# Board_Schamatic06.net
KiCad netlist of a schematic drawn in EAGLE
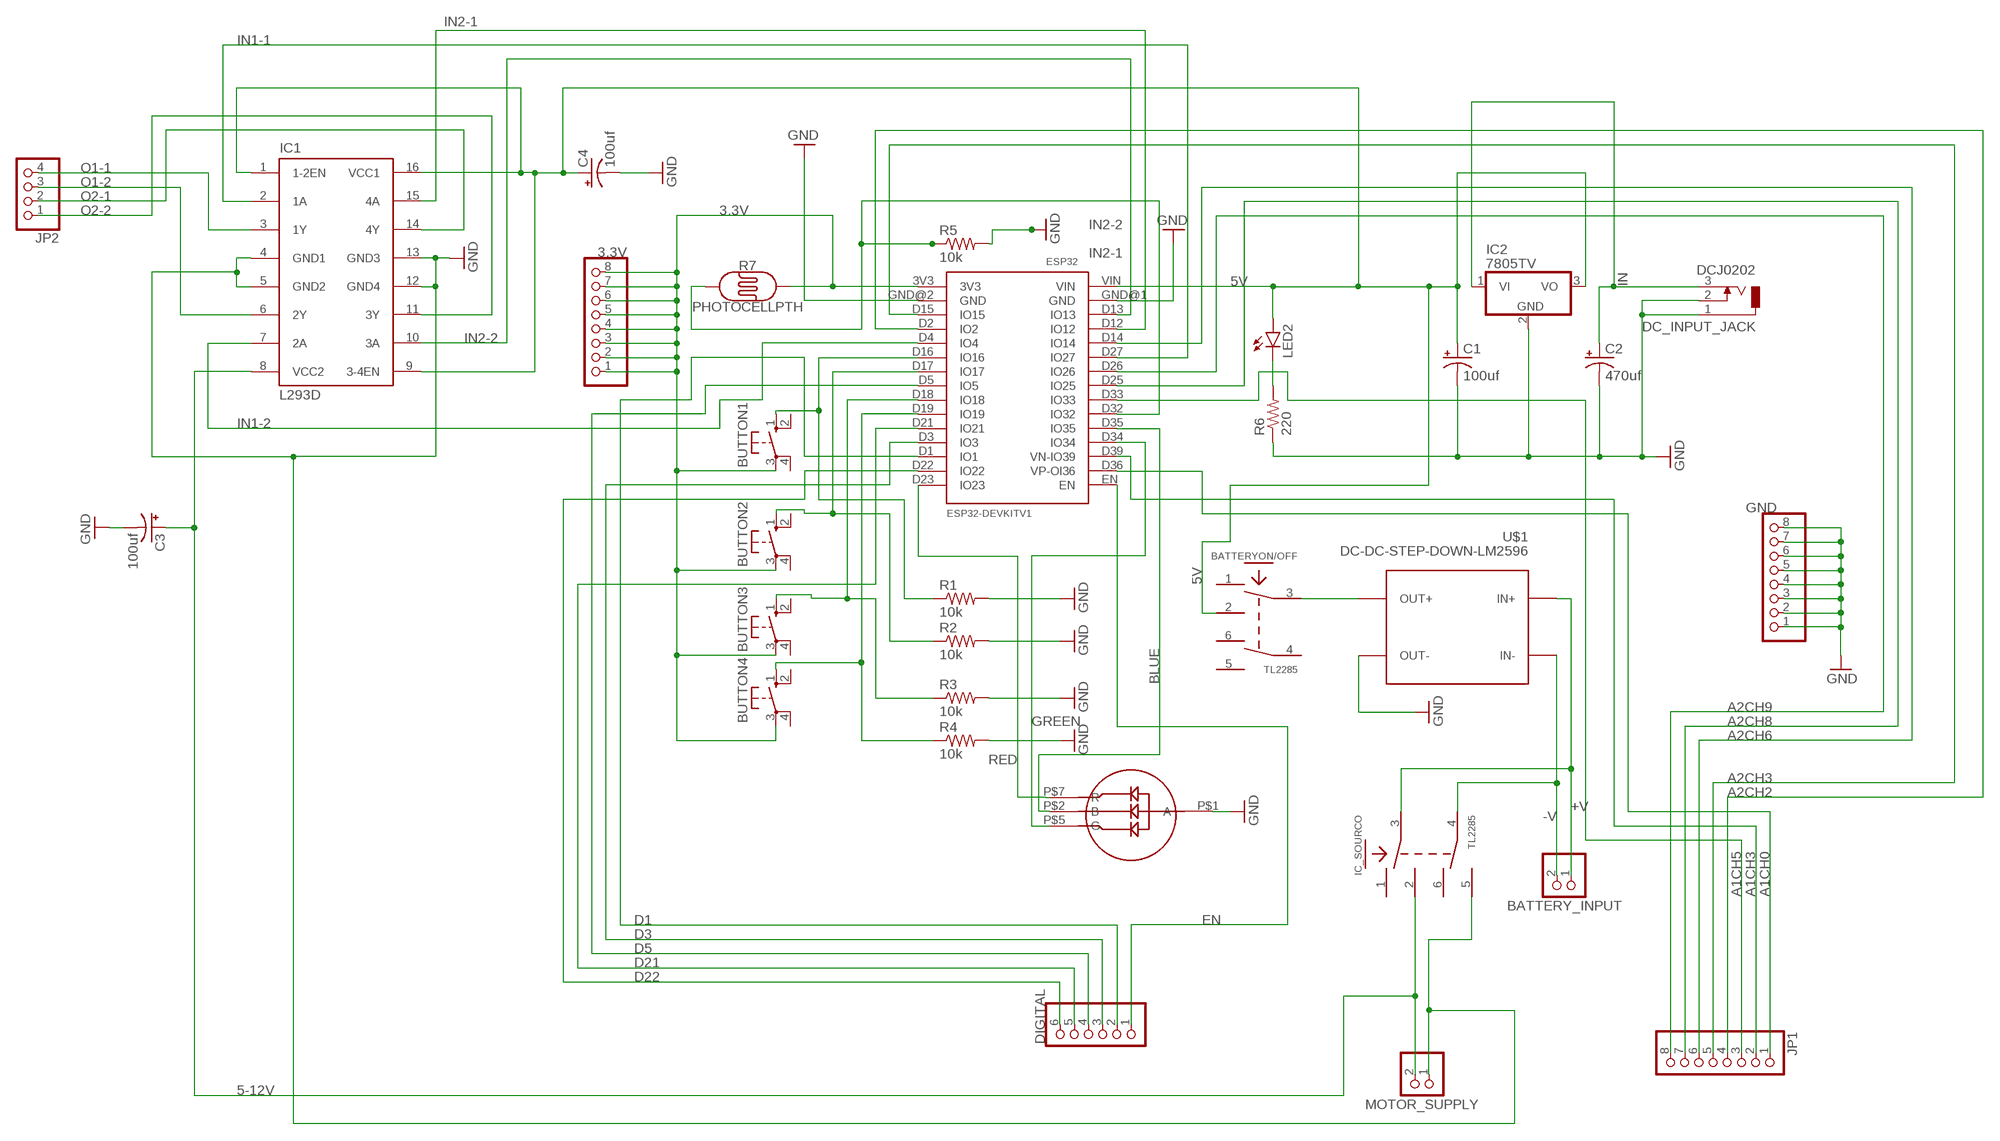
[diagram p0: schematic, sheet 1]

(export (version "E")
  (design (tool "Eeschema 10.0.6"))
  (components
    (comp (ref "3.3V")
      (value "PINHD-1X8")
      (footprint "eagle-import:1X08")
      (libsource (lib "eagle-import") (part "PINHD-1X8"))
    )
    (comp (ref "BATTERYON/OFF")
      (value "TL2285")
      (footprint "eagle-import:TL2285_PCB")
      (libsource (lib "eagle-import") (part "TL2285"))
    )
    (comp (ref "BATTERY_INPUT")
      (value "PINHD-1X2")
      (footprint "eagle-import:1X02")
      (libsource (lib "eagle-import") (part "PINHD-1X2"))
    )
    (comp (ref "BUTTON1")
      (value "10-XX")
      (footprint "eagle-import:B3F-10XX")
      (fields (field (name "MPN") "B3F-1000"))
      (libsource (lib "eagle-import") (part "10-XX"))
    )
    (comp (ref "BUTTON2")
      (value "10-XX")
      (footprint "eagle-import:B3F-10XX")
      (fields (field (name "MPN") "B3F-1000"))
      (libsource (lib "eagle-import") (part "10-XX"))
    )
    (comp (ref "BUTTON3")
      (value "10-XX")
      (footprint "eagle-import:B3F-10XX")
      (fields (field (name "MPN") "B3F-1000"))
      (libsource (lib "eagle-import") (part "10-XX"))
    )
    (comp (ref "BUTTON4")
      (value "10-XX")
      (footprint "eagle-import:B3F-10XX")
      (fields (field (name "MPN") "B3F-1000"))
      (libsource (lib "eagle-import") (part "10-XX"))
    )
    (comp (ref "C1")
      (value "100uf")
      (footprint "eagle-import:E2-5")
      (libsource (lib "eagle-import") (part "CPOL-USE2-5"))
    )
    (comp (ref "C2")
      (value "470uf")
      (footprint "eagle-import:E2-5")
      (libsource (lib "eagle-import") (part "CPOL-USE2-5"))
    )
    (comp (ref "C3")
      (value "100uf")
      (footprint "eagle-import:E2-5")
      (libsource (lib "eagle-import") (part "CPOL-USE2-5"))
    )
    (comp (ref "C4")
      (value "100uf")
      (footprint "eagle-import:E2-5")
      (libsource (lib "eagle-import") (part "CPOL-USE2-5"))
    )
    (comp (ref "DC_INPUT_JACK")
      (value "DCJ0202")
      (footprint "eagle-import:DCJ0202")
      (libsource (lib "eagle-import") (part "DCJ0202"))
    )
    (comp (ref "DIGITAL")
      (value "PINHD-1X6")
      (footprint "eagle-import:1X06")
      (libsource (lib "eagle-import") (part "PINHD-1X6"))
    )
    (comp (ref "ESP32")
      (value "ESP32DEVKITV1")
      (footprint "eagle-import:ESP32-DEVKITV1")
      (libsource (lib "eagle-import") (part "ESP32DEVKITV1"))
    )
    (comp (ref "GND")
      (value "PINHD-1X8")
      (footprint "eagle-import:1X08")
      (libsource (lib "eagle-import") (part "PINHD-1X8"))
    )
    (comp (ref "IC1")
      (value "L293D")
      (footprint "eagle-import:DIL16")
      (libsource (lib "eagle-import") (part "L293D"))
    )
    (comp (ref "IC2")
      (value "7805TV")
      (footprint "eagle-import:TO220V")
      (libsource (lib "eagle-import") (part "78TV05"))
    )
    (comp (ref "IC_SOURCO")
      (value "TL2285")
      (footprint "eagle-import:TL2285_PCB")
      (libsource (lib "eagle-import") (part "TL2285"))
    )
    (comp (ref "JP1")
      (value "PINHD-1X8")
      (footprint "eagle-import:1X08")
      (libsource (lib "eagle-import") (part "PINHD-1X8"))
    )
    (comp (ref "JP2")
      (value "PINHD-1X4")
      (footprint "eagle-import:1X04")
      (libsource (lib "eagle-import") (part "PINHD-1X4"))
    )
    (comp (ref "LED-4_PIN1")
      (value "LED-4_PIN")
      (footprint "eagle-import:LED-4_PIN")
      (libsource (lib "eagle-import") (part "LED-4_PIN"))
    )
    (comp (ref "LED2")
      (value "LED5MM")
      (footprint "eagle-import:LED5MM")
      (libsource (lib "eagle-import") (part "LED5MM"))
    )
    (comp (ref "MOTOR_SUPPLY")
      (value "PINHD-1X2")
      (footprint "eagle-import:1X02")
      (libsource (lib "eagle-import") (part "PINHD-1X2"))
    )
    (comp (ref "R1")
      (value "10k")
      (footprint "eagle-import:0207_10")
      (libsource (lib "eagle-import") (part "R-US_0207/10"))
    )
    (comp (ref "R2")
      (value "10k")
      (footprint "eagle-import:0207_10")
      (libsource (lib "eagle-import") (part "R-US_0207/10"))
    )
    (comp (ref "R3")
      (value "10k")
      (footprint "eagle-import:0207_10")
      (libsource (lib "eagle-import") (part "R-US_0207/10"))
    )
    (comp (ref "R4")
      (value "10k")
      (footprint "eagle-import:0207_10")
      (libsource (lib "eagle-import") (part "R-US_0207/10"))
    )
    (comp (ref "R5")
      (value "10k")
      (footprint "eagle-import:0207_10")
      (libsource (lib "eagle-import") (part "R-US_0207/10"))
    )
    (comp (ref "R6")
      (value "220")
      (footprint "eagle-import:0207_10")
      (libsource (lib "eagle-import") (part "R-US_0207/10"))
    )
    (comp (ref "R7")
      (value "PHOTOCELLPTH")
      (footprint "eagle-import:PHOTOCELL")
      (libsource (lib "eagle-import") (part "PHOTOCELLPTH"))
    )
    (comp (ref "U$1")
      (value "DC-DC-STEP-DOWN-LM2596")
      (footprint "eagle-import:DC-DC-STEP-DOWN-LM2596")
      (libsource (lib "eagle-import") (part "DC-DC-STEP-DOWN-LM2596"))
    )
  )
  (nets
    (net (code "1") (name "/+V") (class "Default")
      (node (ref "BATTERY_INPUT") (pin "1") (pinfunction "1_1") (pintype "passive"))
      (node (ref "IC_SOURCO") (pin "3") (pinfunction "P3_3") (pintype "bidirectional"))
      (node (ref "U$1") (pin "IN+") (pinfunction "IN+_IN+") (pintype "bidirectional"))
    )
    (net (code "2") (name "/-V") (class "Default")
      (node (ref "BATTERY_INPUT") (pin "2") (pinfunction "2_2") (pintype "passive"))
      (node (ref "IC_SOURCO") (pin "4") (pinfunction "P4_4") (pintype "bidirectional"))
      (node (ref "U$1") (pin "IN-") (pinfunction "IN-_IN-") (pintype "bidirectional"))
    )
    (net (code "3") (name "/3.3V") (class "Default")
      (node (ref "3.3V") (pin "1") (pinfunction "1_1") (pintype "passive"))
      (node (ref "3.3V") (pin "2") (pinfunction "2_2") (pintype "passive"))
      (node (ref "3.3V") (pin "3") (pinfunction "3_3") (pintype "passive"))
      (node (ref "3.3V") (pin "4") (pinfunction "4_4") (pintype "passive"))
      (node (ref "3.3V") (pin "5") (pinfunction "5_5") (pintype "passive"))
      (node (ref "3.3V") (pin "6") (pinfunction "6_6") (pintype "passive"))
      (node (ref "3.3V") (pin "7") (pinfunction "7_7") (pintype "passive"))
      (node (ref "3.3V") (pin "8") (pinfunction "8_8") (pintype "passive"))
      (node (ref "BUTTON1") (pin "3") (pinfunction "P_3") (pintype "passive"))
      (node (ref "BUTTON2") (pin "3") (pinfunction "P_3") (pintype "passive"))
      (node (ref "BUTTON3") (pin "3") (pinfunction "P_3") (pintype "passive"))
      (node (ref "BUTTON4") (pin "3") (pinfunction "P_3") (pintype "passive"))
      (node (ref "ESP32") (pin "3V3") (pinfunction "3V3_3V3") (pintype "bidirectional"))
      (node (ref "R7") (pin "2") (pinfunction "P$2_2") (pintype "bidirectional"))
    )
    (net (code "4") (name "/5-12V") (class "Default")
      (node (ref "C3") (pin "+") (pinfunction "+_+") (pintype "passive"))
      (node (ref "IC1") (pin "8") (pinfunction "VCC2_8") (pintype "power_in"))
      (node (ref "IC_SOURCO") (pin "2") (pinfunction "P2_2") (pintype "bidirectional"))
      (node (ref "MOTOR_SUPPLY") (pin "2") (pinfunction "2_2") (pintype "passive"))
    )
    (net (code "5") (name "/5V") (class "Default")
      (node (ref "BATTERYON/OFF") (pin "2") (pinfunction "P2_2") (pintype "bidirectional"))
      (node (ref "C1") (pin "+") (pinfunction "+_+") (pintype "passive"))
      (node (ref "C4") (pin "+") (pinfunction "+_+") (pintype "passive"))
      (node (ref "ESP32") (pin "VIN") (pinfunction "VIN_VIN") (pintype "bidirectional"))
      (node (ref "IC1") (pin "1") (pinfunction "1-2EN_1") (pintype "input"))
      (node (ref "IC1") (pin "16") (pinfunction "VCC1_16") (pintype "power_in"))
      (node (ref "IC1") (pin "9") (pinfunction "3-4EN_9") (pintype "input"))
      (node (ref "IC2") (pin "3") (pinfunction "VO_3") (pintype "passive"))
      (node (ref "LED2") (pin "A") (pinfunction "A_A") (pintype "passive"))
    )
    (net (code "6") (name "/A1CH0") (class "Default")
      (node (ref "ESP32") (pin "D36") (pinfunction "VP-OI36_D36") (pintype "bidirectional"))
      (node (ref "JP1") (pin "1") (pinfunction "1_1") (pintype "passive"))
    )
    (net (code "7") (name "/A1CH3") (class "Default")
      (node (ref "ESP32") (pin "D39") (pinfunction "VN-IO39_D39") (pintype "bidirectional"))
      (node (ref "JP1") (pin "2") (pinfunction "2_2") (pintype "passive"))
    )
    (net (code "8") (name "/A1CH5") (class "Default")
      (node (ref "ESP32") (pin "D33") (pinfunction "IO33_D33") (pintype "bidirectional"))
      (node (ref "JP1") (pin "3") (pinfunction "3_3") (pintype "passive"))
    )
    (net (code "9") (name "/A2CH2") (class "Default")
      (node (ref "ESP32") (pin "D2") (pinfunction "IO2_D2") (pintype "bidirectional"))
      (node (ref "JP1") (pin "4") (pinfunction "4_4") (pintype "passive"))
    )
    (net (code "10") (name "/A2CH3") (class "Default")
      (node (ref "ESP32") (pin "D15") (pinfunction "IO15_D15") (pintype "bidirectional"))
      (node (ref "JP1") (pin "5") (pinfunction "5_5") (pintype "passive"))
    )
    (net (code "11") (name "/A2CH6") (class "Default")
      (node (ref "ESP32") (pin "D14") (pinfunction "IO14_D14") (pintype "bidirectional"))
      (node (ref "JP1") (pin "6") (pinfunction "6_6") (pintype "passive"))
    )
    (net (code "12") (name "/A2CH8") (class "Default")
      (node (ref "ESP32") (pin "D25") (pinfunction "IO25_D25") (pintype "bidirectional"))
      (node (ref "JP1") (pin "7") (pinfunction "7_7") (pintype "passive"))
    )
    (net (code "13") (name "/A2CH9") (class "Default")
      (node (ref "ESP32") (pin "D26") (pinfunction "IO26_D26") (pintype "bidirectional"))
      (node (ref "JP1") (pin "8") (pinfunction "8_8") (pintype "passive"))
    )
    (net (code "14") (name "/BLUE") (class "Default")
      (node (ref "ESP32") (pin "D35") (pinfunction "IO35_D35") (pintype "bidirectional"))
      (node (ref "LED-4_PIN1") (pin "P$2") (pinfunction "B_P$2") (pintype "bidirectional"))
    )
    (net (code "15") (name "/D1") (class "Default")
      (node (ref "DIGITAL") (pin "2") (pinfunction "2_2") (pintype "passive"))
      (node (ref "ESP32") (pin "D1") (pinfunction "IO1_D1") (pintype "bidirectional"))
    )
    (net (code "16") (name "/D3") (class "Default")
      (node (ref "DIGITAL") (pin "3") (pinfunction "3_3") (pintype "passive"))
      (node (ref "ESP32") (pin "D3") (pinfunction "IO3_D3") (pintype "bidirectional"))
    )
    (net (code "17") (name "/D5") (class "Default")
      (node (ref "DIGITAL") (pin "4") (pinfunction "4_4") (pintype "passive"))
      (node (ref "ESP32") (pin "D5") (pinfunction "IO5_D5") (pintype "bidirectional"))
    )
    (net (code "18") (name "/D21") (class "Default")
      (node (ref "DIGITAL") (pin "5") (pinfunction "5_5") (pintype "passive"))
      (node (ref "ESP32") (pin "D21") (pinfunction "IO21_D21") (pintype "bidirectional"))
    )
    (net (code "19") (name "/D22") (class "Default")
      (node (ref "DIGITAL") (pin "6") (pinfunction "6_6") (pintype "passive"))
      (node (ref "ESP32") (pin "D22") (pinfunction "IO22_D22") (pintype "bidirectional"))
    )
    (net (code "20") (name "/EN") (class "Default")
      (node (ref "DIGITAL") (pin "1") (pinfunction "1_1") (pintype "passive"))
      (node (ref "ESP32") (pin "EN") (pinfunction "EN_EN") (pintype "bidirectional"))
    )
    (net (code "21") (name "/GREEN") (class "Default")
      (node (ref "ESP32") (pin "D34") (pinfunction "IO34_D34") (pintype "bidirectional"))
      (node (ref "LED-4_PIN1") (pin "P$5") (pinfunction "G_P$5") (pintype "bidirectional"))
    )
    (net (code "22") (name "/IN") (class "Default")
      (node (ref "C2") (pin "+") (pinfunction "+_+") (pintype "passive"))
      (node (ref "DC_INPUT_JACK") (pin "3") (pinfunction "3_3") (pintype "passive"))
      (node (ref "IC2") (pin "1") (pinfunction "VI_1") (pintype "input"))
    )
    (net (code "23") (name "/IN1-1") (class "Default")
      (node (ref "ESP32") (pin "D27") (pinfunction "IO27_D27") (pintype "bidirectional"))
      (node (ref "IC1") (pin "2") (pinfunction "1A_2") (pintype "input"))
    )
    (net (code "24") (name "/IN1-2") (class "Default")
      (node (ref "ESP32") (pin "D4") (pinfunction "IO4_D4") (pintype "bidirectional"))
      (node (ref "IC1") (pin "7") (pinfunction "2A_7") (pintype "input"))
    )
    (net (code "25") (name "/IN2-1") (class "Default")
      (node (ref "ESP32") (pin "D12") (pinfunction "IO12_D12") (pintype "bidirectional"))
      (node (ref "IC1") (pin "15") (pinfunction "4A_15") (pintype "input"))
    )
    (net (code "26") (name "/IN2-2") (class "Default")
      (node (ref "ESP32") (pin "D13") (pinfunction "IO13_D13") (pintype "bidirectional"))
      (node (ref "IC1") (pin "10") (pinfunction "3A_10") (pintype "input"))
    )
    (net (code "27") (name "/O1-1") (class "Default")
      (node (ref "IC1") (pin "3") (pinfunction "1Y_3") (pintype "output"))
      (node (ref "JP2") (pin "4") (pinfunction "4_4") (pintype "passive"))
    )
    (net (code "28") (name "/O1-2") (class "Default")
      (node (ref "IC1") (pin "6") (pinfunction "2Y_6") (pintype "output"))
      (node (ref "JP2") (pin "3") (pinfunction "3_3") (pintype "passive"))
    )
    (net (code "29") (name "/O2-1") (class "Default")
      (node (ref "IC1") (pin "14") (pinfunction "4Y_14") (pintype "output"))
      (node (ref "JP2") (pin "2") (pinfunction "2_2") (pintype "passive"))
    )
    (net (code "30") (name "/O2-2") (class "Default")
      (node (ref "IC1") (pin "11") (pinfunction "3Y_11") (pintype "output"))
      (node (ref "JP2") (pin "1") (pinfunction "1_1") (pintype "passive"))
    )
    (net (code "31") (name "/RED") (class "Default")
      (node (ref "ESP32") (pin "D23") (pinfunction "IO23_D23") (pintype "bidirectional"))
      (node (ref "LED-4_PIN1") (pin "P$7") (pinfunction "R_P$7") (pintype "bidirectional"))
    )
    (net (code "32") (name "GND") (class "Default")
      (node (ref "C1") (pin "-") (pinfunction "-_-") (pintype "passive"))
      (node (ref "C2") (pin "-") (pinfunction "-_-") (pintype "passive"))
      (node (ref "C3") (pin "-") (pinfunction "-_-") (pintype "passive"))
      (node (ref "C4") (pin "-") (pinfunction "-_-") (pintype "passive"))
      (node (ref "DC_INPUT_JACK") (pin "1") (pinfunction "1_1") (pintype "passive"))
      (node (ref "DC_INPUT_JACK") (pin "2") (pinfunction "2_2") (pintype "passive"))
      (node (ref "ESP32") (pin "GND@1") (pinfunction "GND_GND@1") (pintype "bidirectional"))
      (node (ref "ESP32") (pin "GND@2") (pinfunction "GND_GND@2") (pintype "bidirectional"))
      (node (ref "GND") (pin "1") (pinfunction "1_1") (pintype "passive"))
      (node (ref "GND") (pin "2") (pinfunction "2_2") (pintype "passive"))
      (node (ref "GND") (pin "3") (pinfunction "3_3") (pintype "passive"))
      (node (ref "GND") (pin "4") (pinfunction "4_4") (pintype "passive"))
      (node (ref "GND") (pin "5") (pinfunction "5_5") (pintype "passive"))
      (node (ref "GND") (pin "6") (pinfunction "6_6") (pintype "passive"))
      (node (ref "GND") (pin "7") (pinfunction "7_7") (pintype "passive"))
      (node (ref "GND") (pin "8") (pinfunction "8_8") (pintype "passive"))
      (node (ref "IC1") (pin "12") (pinfunction "GND4_12") (pintype "power_in"))
      (node (ref "IC1") (pin "13") (pinfunction "GND3_13") (pintype "power_in"))
      (node (ref "IC1") (pin "4") (pinfunction "GND1_4") (pintype "power_in"))
      (node (ref "IC1") (pin "5") (pinfunction "GND2_5") (pintype "power_in"))
      (node (ref "IC2") (pin "2") (pinfunction "GND_2") (pintype "passive"))
      (node (ref "IC_SOURCO") (pin "5") (pinfunction "P5_5") (pintype "bidirectional"))
      (node (ref "LED-4_PIN1") (pin "P$1") (pinfunction "A_P$1") (pintype "bidirectional"))
      (node (ref "MOTOR_SUPPLY") (pin "1") (pinfunction "1_1") (pintype "passive"))
      (node (ref "R1") (pin "2") (pinfunction "2_2") (pintype "passive"))
      (node (ref "R2") (pin "2") (pinfunction "2_2") (pintype "passive"))
      (node (ref "R3") (pin "2") (pinfunction "2_2") (pintype "passive"))
      (node (ref "R4") (pin "2") (pinfunction "2_2") (pintype "passive"))
      (node (ref "R5") (pin "2") (pinfunction "2_2") (pintype "passive"))
      (node (ref "R6") (pin "1") (pinfunction "1_1") (pintype "passive"))
      (node (ref "U$1") (pin "OUT-") (pinfunction "OUT-_OUT-") (pintype "bidirectional"))
    )
    (net (code "33") (name "Net-(BATTERYON/OFF-P3)") (class "Default")
      (node (ref "BATTERYON/OFF") (pin "3") (pinfunction "P3_3") (pintype "bidirectional"))
      (node (ref "U$1") (pin "OUT+") (pinfunction "OUT+_OUT+") (pintype "bidirectional"))
    )
    (net (code "34") (name "Net-(BUTTON1-S)") (class "Default")
      (node (ref "BUTTON1") (pin "1") (pinfunction "S_1") (pintype "passive"))
      (node (ref "ESP32") (pin "D16") (pinfunction "IO16_D16") (pintype "bidirectional"))
      (node (ref "R1") (pin "1") (pinfunction "1_1") (pintype "passive"))
    )
    (net (code "35") (name "Net-(BUTTON2-S)") (class "Default")
      (node (ref "BUTTON2") (pin "1") (pinfunction "S_1") (pintype "passive"))
      (node (ref "ESP32") (pin "D17") (pinfunction "IO17_D17") (pintype "bidirectional"))
      (node (ref "R2") (pin "1") (pinfunction "1_1") (pintype "passive"))
    )
    (net (code "36") (name "Net-(BUTTON3-S)") (class "Default")
      (node (ref "BUTTON3") (pin "1") (pinfunction "S_1") (pintype "passive"))
      (node (ref "ESP32") (pin "D18") (pinfunction "IO18_D18") (pintype "bidirectional"))
      (node (ref "R3") (pin "1") (pinfunction "1_1") (pintype "passive"))
    )
    (net (code "37") (name "Net-(BUTTON4-S)") (class "Default")
      (node (ref "BUTTON4") (pin "1") (pinfunction "S_1") (pintype "passive"))
      (node (ref "ESP32") (pin "D19") (pinfunction "IO19_D19") (pintype "bidirectional"))
      (node (ref "R4") (pin "1") (pinfunction "1_1") (pintype "passive"))
    )
    (net (code "38") (name "Net-(ESP32-IO32)") (class "Default")
      (node (ref "ESP32") (pin "D32") (pinfunction "IO32_D32") (pintype "bidirectional"))
      (node (ref "R5") (pin "1") (pinfunction "1_1") (pintype "passive"))
      (node (ref "R7") (pin "1") (pinfunction "P$1_1") (pintype "bidirectional"))
    )
    (net (code "39") (name "Net-(LED2-C)") (class "Default")
      (node (ref "LED2") (pin "K") (pinfunction "C_K") (pintype "passive"))
      (node (ref "R6") (pin "2") (pinfunction "2_2") (pintype "passive"))
    )
    (net (code "40") (name "unconnected-(BATTERYON/OFF-P1-Pad1)") (class "Default")
      (node (ref "BATTERYON/OFF") (pin "1") (pinfunction "P1_1") (pintype "bidirectional"))
    )
    (net (code "41") (name "unconnected-(BATTERYON/OFF-P4-Pad4)") (class "Default")
      (node (ref "BATTERYON/OFF") (pin "4") (pinfunction "P4_4") (pintype "bidirectional"))
    )
    (net (code "42") (name "unconnected-(BATTERYON/OFF-P5-Pad5)") (class "Default")
      (node (ref "BATTERYON/OFF") (pin "5") (pinfunction "P5_5") (pintype "bidirectional"))
    )
    (net (code "43") (name "unconnected-(BATTERYON/OFF-P6-Pad6)") (class "Default")
      (node (ref "BATTERYON/OFF") (pin "6") (pinfunction "P6_6") (pintype "bidirectional"))
    )
    (net (code "44") (name "unconnected-(BUTTON1-P1-Pad4)") (class "Default")
      (node (ref "BUTTON1") (pin "4") (pinfunction "P1_4") (pintype "passive"))
    )
    (net (code "45") (name "unconnected-(BUTTON1-S1-Pad2)") (class "Default")
      (node (ref "BUTTON1") (pin "2") (pinfunction "S1_2") (pintype "passive"))
    )
    (net (code "46") (name "unconnected-(BUTTON2-P1-Pad4)") (class "Default")
      (node (ref "BUTTON2") (pin "4") (pinfunction "P1_4") (pintype "passive"))
    )
    (net (code "47") (name "unconnected-(BUTTON2-S1-Pad2)") (class "Default")
      (node (ref "BUTTON2") (pin "2") (pinfunction "S1_2") (pintype "passive"))
    )
    (net (code "48") (name "unconnected-(BUTTON3-P1-Pad4)") (class "Default")
      (node (ref "BUTTON3") (pin "4") (pinfunction "P1_4") (pintype "passive"))
    )
    (net (code "49") (name "unconnected-(BUTTON3-S1-Pad2)") (class "Default")
      (node (ref "BUTTON3") (pin "2") (pinfunction "S1_2") (pintype "passive"))
    )
    (net (code "50") (name "unconnected-(BUTTON4-P1-Pad4)") (class "Default")
      (node (ref "BUTTON4") (pin "4") (pinfunction "P1_4") (pintype "passive"))
    )
    (net (code "51") (name "unconnected-(BUTTON4-S1-Pad2)") (class "Default")
      (node (ref "BUTTON4") (pin "2") (pinfunction "S1_2") (pintype "passive"))
    )
    (net (code "52") (name "unconnected-(IC_SOURCO-P1-Pad1)") (class "Default")
      (node (ref "IC_SOURCO") (pin "1") (pinfunction "P1_1") (pintype "bidirectional"))
    )
    (net (code "53") (name "unconnected-(IC_SOURCO-P6-Pad6)") (class "Default")
      (node (ref "IC_SOURCO") (pin "6") (pinfunction "P6_6") (pintype "bidirectional"))
    )
  )
)
